# Main.net
KiCad netlist of a schematic drawn in Altium Designer
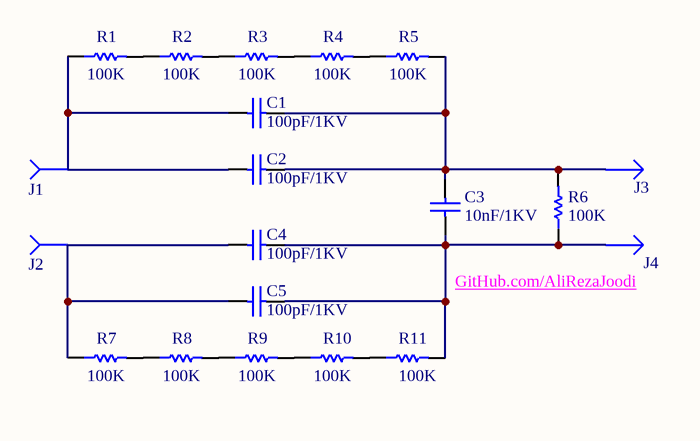
[diagram p0: Main.SchDoc]

(export (version "E")
  (design (tool "Eeschema 10.0.6"))
  (components
    (comp (ref "C1")
      (value "100pF/1KV")
      (footprint "THD_P5.08/D4.2/T2")
      (description "Capacitor, Ceramic Multilayer")
      (libsource (lib "General") (part "Capacitor_Ceramic"))
    )
    (comp (ref "C2")
      (value "100pF/1KV")
      (footprint "THD_P5.08/D4.2/T2")
      (description "Capacitor, Ceramic Multilayer")
      (libsource (lib "General") (part "Capacitor_Ceramic"))
    )
    (comp (ref "C3")
      (value "10nF/1KV")
      (footprint "THD_P5.08/D4.2/T2")
      (description "Capacitor, Ceramic Multilayer")
      (libsource (lib "General") (part "Capacitor_Ceramic"))
    )
    (comp (ref "C4")
      (value "100pF/1KV")
      (footprint "THD_P5.08/D4.2/T2")
      (description "Capacitor, Ceramic Multilayer")
      (libsource (lib "General") (part "Capacitor_Ceramic"))
    )
    (comp (ref "C5")
      (value "100pF/1KV")
      (footprint "THD_P5.08/D4.2/T2")
      (description "Capacitor, Ceramic Multilayer")
      (libsource (lib "General") (part "Capacitor_Ceramic"))
    )
    (comp (ref "J1")
      (value "~")
      (description "Lable Connector, Socket, 1Pin")
      (libsource (lib "Connector") (part "Connector_Socket_1Pin_Female_Lable"))
    )
    (comp (ref "J2")
      (value "~")
      (description "Lable Connector, Socket, 1Pin")
      (libsource (lib "Connector") (part "Connector_Socket_1Pin_Female_Lable"))
    )
    (comp (ref "J3")
      (value "~")
      (description "Lable Connector, Socket, 1Pin")
      (libsource (lib "Connector") (part "Connector_Socket_1Pin_Male_Lable"))
    )
    (comp (ref "J4")
      (value "~")
      (description "Lable Connector, Socket, 1Pin")
      (libsource (lib "Connector") (part "Connector_Socket_1Pin_Male_Lable"))
    )
    (comp (ref "R1")
      (value "100K")
      (footprint "THD_AXIAL0.4")
      (description "Resistor, 1/4W, 5%")
      (libsource (lib "General") (part "Resistor_2Form"))
    )
    (comp (ref "R2")
      (value "100K")
      (footprint "THD_AXIAL0.4")
      (description "Resistor, 1/4W, 5%")
      (libsource (lib "General") (part "Resistor_2Form"))
    )
    (comp (ref "R3")
      (value "100K")
      (footprint "THD_AXIAL0.4")
      (description "Resistor, 1/4W, 5%")
      (libsource (lib "General") (part "Resistor_2Form"))
    )
    (comp (ref "R4")
      (value "100K")
      (footprint "THD_AXIAL0.4")
      (description "Resistor, 1/4W, 5%")
      (libsource (lib "General") (part "Resistor_2Form"))
    )
    (comp (ref "R5")
      (value "100K")
      (footprint "THD_AXIAL0.4")
      (description "Resistor, 1/4W, 5%")
      (libsource (lib "General") (part "Resistor_2Form"))
    )
    (comp (ref "R6")
      (value "100K")
      (footprint "THD_AXIAL0.4")
      (description "Resistor, 1/4W, 5%")
      (libsource (lib "General") (part "Resistor_2Form"))
    )
    (comp (ref "R7")
      (value "100K")
      (footprint "THD_AXIAL0.4")
      (description "Resistor, 1/4W, 5%")
      (libsource (lib "General") (part "Resistor_2Form"))
    )
    (comp (ref "R8")
      (value "100K")
      (footprint "THD_AXIAL0.4")
      (description "Resistor, 1/4W, 5%")
      (libsource (lib "General") (part "Resistor_2Form"))
    )
    (comp (ref "R9")
      (value "100K")
      (footprint "THD_AXIAL0.4")
      (description "Resistor, 1/4W, 5%")
      (libsource (lib "General") (part "Resistor_2Form"))
    )
    (comp (ref "R10")
      (value "100K")
      (footprint "THD_AXIAL0.4")
      (description "Resistor, 1/4W, 5%")
      (libsource (lib "General") (part "Resistor_2Form"))
    )
    (comp (ref "R11")
      (value "100K")
      (footprint "THD_AXIAL0.4")
      (description "Resistor, 1/4W, 5%")
      (libsource (lib "General") (part "Resistor_2Form"))
    )
  )
  (nets
    (net (code "1") (name "Net-(C1-Pad1)") (class "Default")
      (node (ref "C1") (pin "1") (pinfunction "1_1") (pintype "passive"))
      (node (ref "C2") (pin "1") (pinfunction "1_1") (pintype "passive"))
      (node (ref "C3") (pin "2") (pinfunction "2_2") (pintype "passive"))
      (node (ref "R5") (pin "1") (pinfunction "1_1") (pintype "passive"))
      (node (ref "R6") (pin "1") (pinfunction "1_1") (pintype "passive"))
    )
    (net (code "2") (name "Net-(C1-Pad2)") (class "Default")
      (node (ref "C1") (pin "2") (pinfunction "2_2") (pintype "passive"))
      (node (ref "C2") (pin "2") (pinfunction "2_2") (pintype "passive"))
      (node (ref "R1") (pin "2") (pinfunction "2_2") (pintype "passive"))
    )
    (net (code "3") (name "Net-(C3-Pad1)") (class "Default")
      (node (ref "C3") (pin "1") (pinfunction "1_1") (pintype "passive"))
      (node (ref "C4") (pin "1") (pinfunction "1_1") (pintype "passive"))
      (node (ref "C5") (pin "1") (pinfunction "1_1") (pintype "passive"))
      (node (ref "R11") (pin "1") (pinfunction "1_1") (pintype "passive"))
      (node (ref "R6") (pin "2") (pinfunction "2_2") (pintype "passive"))
    )
    (net (code "4") (name "Net-(C4-Pad2)") (class "Default")
      (node (ref "C4") (pin "2") (pinfunction "2_2") (pintype "passive"))
      (node (ref "C5") (pin "2") (pinfunction "2_2") (pintype "passive"))
      (node (ref "R7") (pin "2") (pinfunction "2_2") (pintype "passive"))
    )
    (net (code "5") (name "Net-(R1-Pad1)") (class "Default")
      (node (ref "R1") (pin "1") (pinfunction "1_1") (pintype "passive"))
      (node (ref "R2") (pin "2") (pinfunction "2_2") (pintype "passive"))
    )
    (net (code "6") (name "Net-(R2-Pad1)") (class "Default")
      (node (ref "R2") (pin "1") (pinfunction "1_1") (pintype "passive"))
      (node (ref "R3") (pin "2") (pinfunction "2_2") (pintype "passive"))
    )
    (net (code "7") (name "Net-(R3-Pad1)") (class "Default")
      (node (ref "R3") (pin "1") (pinfunction "1_1") (pintype "passive"))
      (node (ref "R4") (pin "2") (pinfunction "2_2") (pintype "passive"))
    )
    (net (code "8") (name "Net-(R4-Pad1)") (class "Default")
      (node (ref "R4") (pin "1") (pinfunction "1_1") (pintype "passive"))
      (node (ref "R5") (pin "2") (pinfunction "2_2") (pintype "passive"))
    )
    (net (code "9") (name "Net-(R7-Pad1)") (class "Default")
      (node (ref "R7") (pin "1") (pinfunction "1_1") (pintype "passive"))
      (node (ref "R8") (pin "2") (pinfunction "2_2") (pintype "passive"))
    )
    (net (code "10") (name "Net-(R8-Pad1)") (class "Default")
      (node (ref "R8") (pin "1") (pinfunction "1_1") (pintype "passive"))
      (node (ref "R9") (pin "2") (pinfunction "2_2") (pintype "passive"))
    )
    (net (code "11") (name "Net-(R10-Pad1)") (class "Default")
      (node (ref "R10") (pin "1") (pinfunction "1_1") (pintype "passive"))
      (node (ref "R11") (pin "2") (pinfunction "2_2") (pintype "passive"))
    )
    (net (code "12") (name "Net-(R10-Pad2)") (class "Default")
      (node (ref "R10") (pin "2") (pinfunction "2_2") (pintype "passive"))
      (node (ref "R9") (pin "1") (pinfunction "1_1") (pintype "passive"))
    )
  )
)
